# PARA_HACER_BODE_Y_PRUEBAS_de_EA.net
KiCad netlist of a schematic drawn in Altium Designer
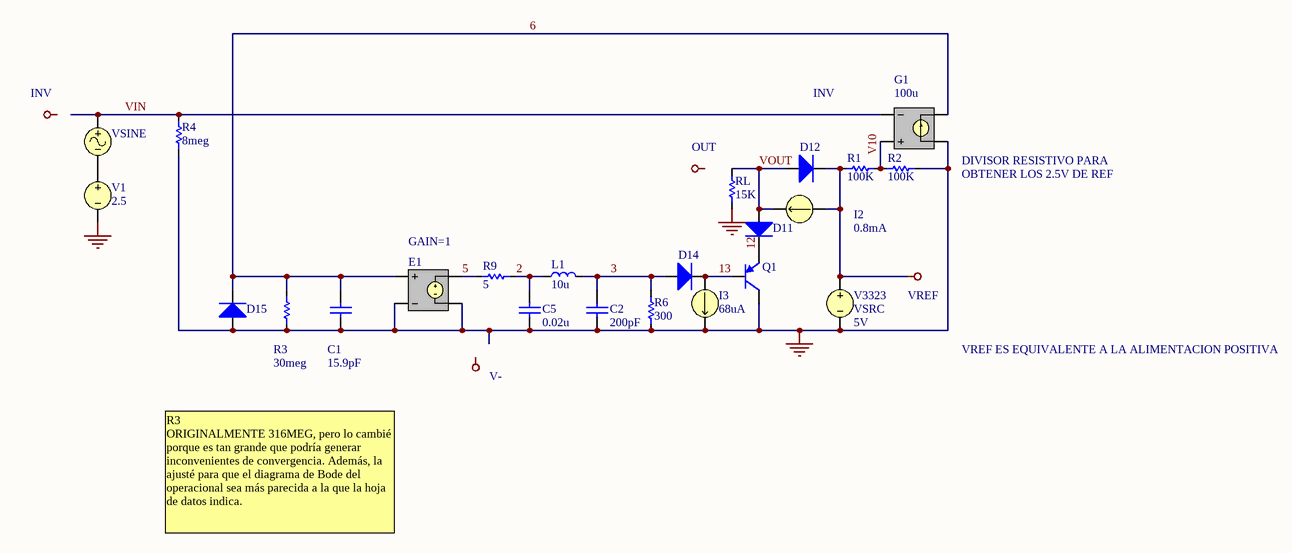
[diagram p0: PARA HACER BODE Y PRUEBAS de EA.SCHDOC]

(export (version "E")
  (design (tool "Eeschema 10.0.6"))
  (components
    (comp (ref "C1")
      (value "15.9pF")
      (footprint "0805")
      (description "Capacitor")
      (fields (field (name "VOLTAGE") "50V") (field (name "Comment") "Cap"))
      (libsource (lib "FEDE") (part "Cap"))
    )
    (comp (ref "C2")
      (value "200pF")
      (footprint "0805")
      (description "Capacitor")
      (fields (field (name "VOLTAGE") "50V") (field (name "Comment") "Cap"))
      (libsource (lib "FEDE") (part "Cap"))
    )
    (comp (ref "C5")
      (value "0.02u")
      (footprint "0805")
      (description "Capacitor")
      (fields (field (name "VOLTAGE") "50V") (field (name "Comment") "Cap"))
      (libsource (lib "FEDE") (part "Cap"))
    )
    (comp (ref "D11")
      (value "Diode")
      (footprint "diode400")
      (description "Diodo")
      (libsource (lib "FEDE") (part "Diode"))
    )
    (comp (ref "D12")
      (value "Diode")
      (footprint "diode400")
      (description "Diodo")
      (libsource (lib "FEDE") (part "Diode"))
    )
    (comp (ref "D14")
      (value "Diode")
      (footprint "diode400")
      (description "Diodo")
      (libsource (lib "FEDE") (part "Diode"))
    )
    (comp (ref "D15")
      (value "Diode")
      (footprint "diode400")
      (description "Diodo")
      (libsource (lib "FEDE") (part "Diode"))
    )
    (comp (ref "E1")
      (value "ESRC")
      (description "Voltage Controlled Voltage Source")
      (fields (field (name "PUBLISHER") "Altium Limited"))
      (libsource (lib "Simulation Sources") (part "ESRC"))
    )
    (comp (ref "G1")
      (value "GSRC")
      (description "Voltage Controlled Current Source")
      (fields (field (name "GAIN") "100u") (field (name "PUBLISHER") "Altium Limited"))
      (libsource (lib "Simulation Sources") (part "GSRC"))
    )
    (comp (ref "I2")
      (value "0.8mA")
      (description "Current Source")
      (fields (field (name "Comment") "ISRC") (field (name "PUBLISHER") "Altium Limited"))
      (libsource (lib "Simulation Sources") (part "ISRC"))
    )
    (comp (ref "I3")
      (value "68uA")
      (description "Current Source")
      (fields (field (name "Comment") "ISRC") (field (name "PUBLISHER") "Altium Limited"))
      (libsource (lib "Simulation Sources") (part "ISRC"))
    )
    (comp (ref "L1")
      (value "10u")
      (footprint "TOROIDE TN14-9-5")
      (description "Inductor")
      (fields (field (name "Comment") "Inductor2"))
      (libsource (lib "FEDE") (part "Inductor2"))
    )
    (comp (ref "Q1")
      (value "PNP")
      (footprint "SOT23")
      (description "PNP Bipolar Transistor")
      (libsource (lib "FEDE") (part "PNP"))
    )
    (comp (ref "R1")
      (value "100K")
      (footprint "0805")
      (description "Resistor")
      (fields (field (name "POWER") "0.25W") (field (name "Comment") "Res"))
      (libsource (lib "FEDE") (part "Res"))
    )
    (comp (ref "R2")
      (value "100K")
      (footprint "0805")
      (description "Resistor")
      (fields (field (name "POWER") "0.25W") (field (name "Comment") "Res"))
      (libsource (lib "FEDE") (part "Res"))
    )
    (comp (ref "R3")
      (value "30meg")
      (footprint "0805")
      (description "Resistor")
      (fields (field (name "POWER") "0.25W") (field (name "Comment") "Res"))
      (libsource (lib "FEDE") (part "Res"))
    )
    (comp (ref "R4")
      (value "8meg")
      (footprint "0805")
      (description "Resistor")
      (fields (field (name "POWER") "0.25W") (field (name "Comment") "Res"))
      (libsource (lib "FEDE") (part "Res"))
    )
    (comp (ref "R6")
      (value "300")
      (footprint "0805")
      (description "Resistor")
      (fields (field (name "POWER") "0.25W") (field (name "Comment") "Res"))
      (libsource (lib "FEDE") (part "Res"))
    )
    (comp (ref "R9")
      (value "5")
      (footprint "0805")
      (description "Resistor")
      (fields (field (name "POWER") "0.25W") (field (name "Comment") "Res"))
      (libsource (lib "FEDE") (part "Res"))
    )
    (comp (ref "RL")
      (value "15K")
      (footprint "0805")
      (description "Resistor")
      (fields (field (name "POWER") "0.25W") (field (name "Comment") "Res"))
      (libsource (lib "FEDE") (part "Res"))
    )
    (comp (ref "V1")
      (value "2.5")
      (description "Voltage Source")
      (fields (field (name "Comment") "VSRC") (field (name "PUBLISHER") "Altium Limited"))
      (libsource (lib "Simulation Sources") (part "VSRC"))
    )
    (comp (ref "V3323")
      (value "VSRC")
      (description "Voltage Source")
      (fields (field (name "ALTIUM_VALUE") "5V") (field (name "PUBLISHER") "Altium Limited"))
      (libsource (lib "Simulation Sources") (part "VSRC"))
    )
    (comp (ref "VSINE")
      (value "VSIN")
      (description "Sinusoidal Voltage Source")
      (fields (field (name "PUBLISHER") "Altium Limited"))
      (libsource (lib "Simulation Sources") (part "VSIN"))
    )
  )
  (nets
    (net (code "1") (name "/2") (class "Default")
      (node (ref "C5") (pin "2") (pinfunction "2_2") (pintype "passive"))
      (node (ref "L1") (pin "1") (pinfunction "1_1") (pintype "passive"))
      (node (ref "R9") (pin "1") (pinfunction "1_1") (pintype "passive"))
    )
    (net (code "2") (name "/3") (class "Default")
      (node (ref "C2") (pin "2") (pinfunction "2_2") (pintype "passive"))
      (node (ref "D14") (pin "1") (pinfunction "1_1") (pintype "passive"))
      (node (ref "L1") (pin "2") (pinfunction "2_2") (pintype "passive"))
      (node (ref "R6") (pin "2") (pinfunction "2_2") (pintype "passive"))
    )
    (net (code "3") (name "/5") (class "Default")
      (node (ref "E1") (pin "3") (pinfunction "N+_3") (pintype "passive"))
      (node (ref "R9") (pin "2") (pinfunction "2_2") (pintype "passive"))
    )
    (net (code "4") (name "/6") (class "Default")
      (node (ref "C1") (pin "2") (pinfunction "2_2") (pintype "passive"))
      (node (ref "D15") (pin "2") (pinfunction "2_2") (pintype "passive"))
      (node (ref "E1") (pin "1") (pinfunction "NC+_1") (pintype "passive"))
      (node (ref "G1") (pin "4") (pinfunction "N-_4") (pintype "passive"))
      (node (ref "R3") (pin "2") (pinfunction "2_2") (pintype "passive"))
    )
    (net (code "5") (name "/12") (class "Default")
      (node (ref "D11") (pin "2") (pinfunction "2_2") (pintype "passive"))
      (node (ref "Q1") (pin "3") (pinfunction "E_3") (pintype "passive"))
    )
    (net (code "6") (name "/13") (class "Default")
      (node (ref "D14") (pin "2") (pinfunction "2_2") (pintype "passive"))
      (node (ref "I3") (pin "1") (pinfunction "1_1") (pintype "passive"))
      (node (ref "Q1") (pin "2") (pinfunction "B_2") (pintype "passive"))
    )
    (net (code "7") (name "/V10") (class "Default")
      (node (ref "G1") (pin "1") (pinfunction "NC+_1") (pintype "passive"))
      (node (ref "R1") (pin "1") (pinfunction "1_1") (pintype "passive"))
      (node (ref "R2") (pin "1") (pinfunction "1_1") (pintype "passive"))
    )
    (net (code "8") (name "/VIN") (class "Default")
      (node (ref "G1") (pin "2") (pinfunction "NC-_2") (pintype "passive"))
      (node (ref "R4") (pin "2") (pinfunction "2_2") (pintype "passive"))
      (node (ref "VSINE") (pin "1") (pinfunction "1_1") (pintype "passive"))
    )
    (net (code "9") (name "/VOUT") (class "Default")
      (node (ref "D11") (pin "1") (pinfunction "1_1") (pintype "passive"))
      (node (ref "D12") (pin "1") (pinfunction "1_1") (pintype "passive"))
      (node (ref "I2") (pin "2") (pinfunction "2_2") (pintype "passive"))
      (node (ref "RL") (pin "2") (pinfunction "2_2") (pintype "passive"))
    )
    (net (code "11") (name "4") (class "Default")
      (node (ref "D12") (pin "2") (pinfunction "2_2") (pintype "passive"))
      (node (ref "I2") (pin "1") (pinfunction "1_1") (pintype "passive"))
      (node (ref "R1") (pin "2") (pinfunction "2_2") (pintype "passive"))
      (node (ref "V3323") (pin "1") (pinfunction "1_1") (pintype "passive"))
    )
    (net (code "14") (name "GND") (class "Default")
      (node (ref "C1") (pin "1") (pinfunction "1_1") (pintype "passive"))
      (node (ref "C2") (pin "1") (pinfunction "1_1") (pintype "passive"))
      (node (ref "C5") (pin "1") (pinfunction "1_1") (pintype "passive"))
      (node (ref "D15") (pin "1") (pinfunction "1_1") (pintype "passive"))
      (node (ref "E1") (pin "2") (pinfunction "NC-_2") (pintype "passive"))
      (node (ref "E1") (pin "4") (pinfunction "N-_4") (pintype "passive"))
      (node (ref "G1") (pin "3") (pinfunction "N+_3") (pintype "passive"))
      (node (ref "I3") (pin "2") (pinfunction "2_2") (pintype "passive"))
      (node (ref "Q1") (pin "1") (pinfunction "C_1") (pintype "passive"))
      (node (ref "R2") (pin "2") (pinfunction "2_2") (pintype "passive"))
      (node (ref "R3") (pin "1") (pinfunction "1_1") (pintype "passive"))
      (node (ref "R4") (pin "1") (pinfunction "1_1") (pintype "passive"))
      (node (ref "R6") (pin "1") (pinfunction "1_1") (pintype "passive"))
      (node (ref "RL") (pin "1") (pinfunction "1_1") (pintype "passive"))
      (node (ref "V1") (pin "2") (pinfunction "2_2") (pintype "passive"))
      (node (ref "V3323") (pin "2") (pinfunction "2_2") (pintype "passive"))
    )
    (net (code "15") (name "Net-(V1-Pad1)") (class "Default")
      (node (ref "V1") (pin "1") (pinfunction "1_1") (pintype "passive"))
      (node (ref "VSINE") (pin "2") (pinfunction "2_2") (pintype "passive"))
    )
  )
)
